# FTDIChip.net
KiCad netlist of a schematic drawn in Altium Designer
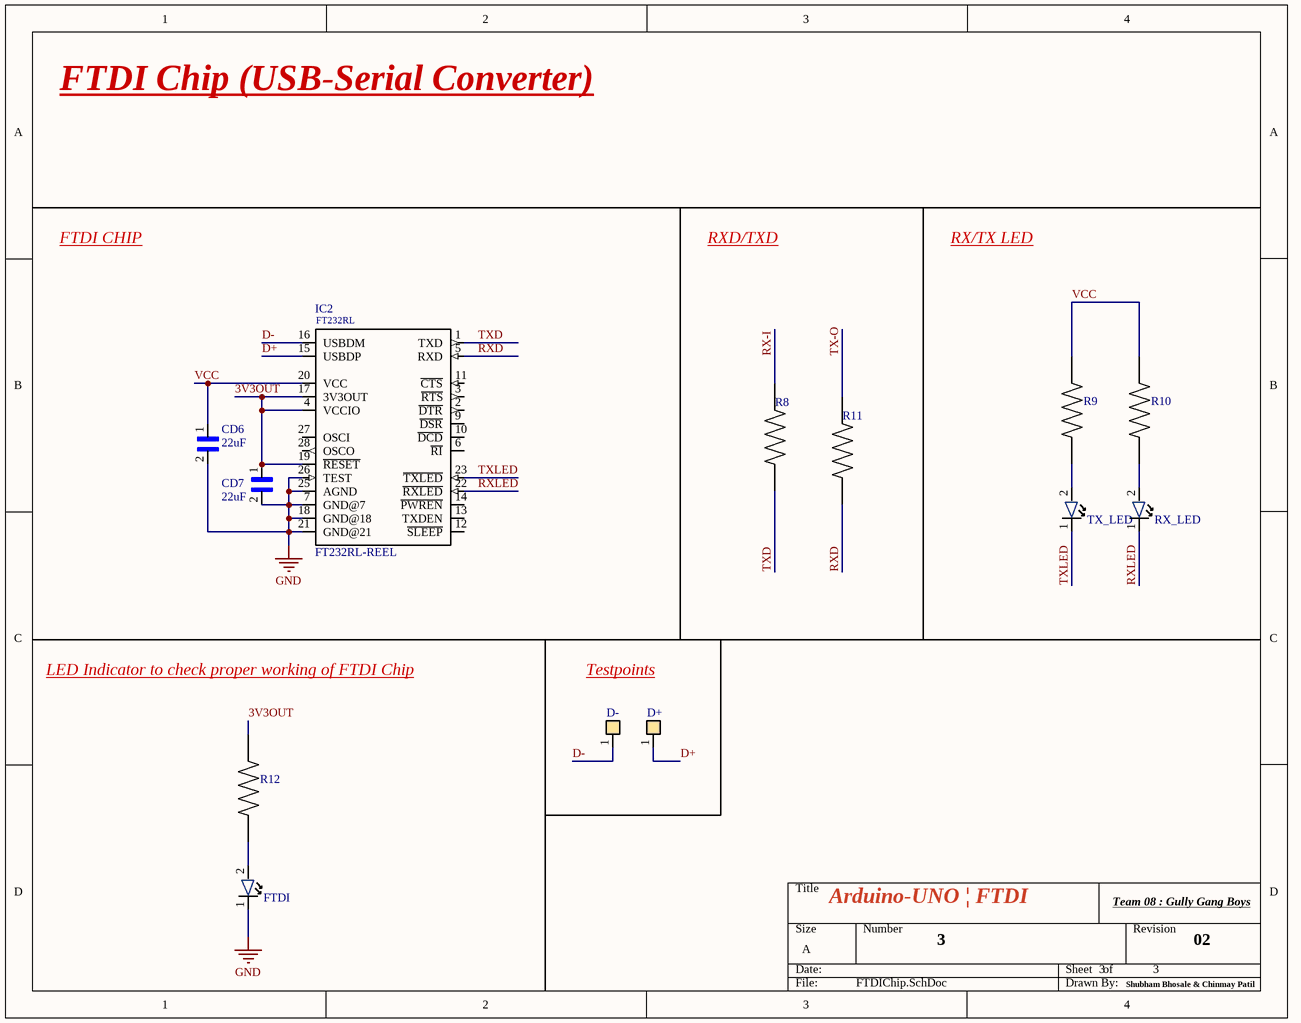
[diagram p0: FTDIChip.SchDoc]

(export (version "E")
  (design (tool "Eeschema 10.0.6"))
  (components
    (comp (ref "CD6")
      (value "22uF")
      (footprint "1206_Passive")
      (description "22µF ±20% 16V Ceramic Capacitor X5R 1206 (3216 Metric)")
      (fields (field (name "DIGIKEY PART") "1276-2728-1-ND"))
      (libsource (lib "brd2_rev2") (part "1206_22uF"))
    )
    (comp (ref "CD7")
      (value "22uF")
      (footprint "1206_Passive")
      (description "22µF ±20% 16V Ceramic Capacitor X5R 1206 (3216 Metric)")
      (fields (field (name "DIGIKEY PART") "1276-2728-1-ND"))
      (libsource (lib "brd2_rev2") (part "1206_22uF"))
    )
    (comp (ref "D+")
      (value "TESTPOINT")
      (footprint "TEST POINT")
      (libsource (lib "brd2_rev2") (part "TEST POINT"))
    )
    (comp (ref "D-")
      (value "TESTPOINT")
      (footprint "TEST POINT")
      (libsource (lib "brd2_rev2") (part "TEST POINT"))
    )
    (comp (ref "FTDI")
      (value "LTST-C150CKT")
      (footprint "LED")
      (description "Red 638nm LED Indication - Discrete 1.8V 1206 (3216 Metric)")
      (fields (field (name "DIGIKEY PART") "160-1167-1-ND"))
      (libsource (lib "brd2_rev2") (part "1206_RED_LED"))
    )
    (comp (ref "IC2")
      (value "FT232RL-REEL")
      (footprint "FTDI")
      (description "USB Bridge, USB to UART USB 2.0 UART Interface 28-SSOP")
      (fields (field (name "DIGIKEY PART") "768-1007-1-ND"))
      (libsource (lib "brd2_rev2") (part "FTDI"))
    )
    (comp (ref "R8")
      (value "RNCP1206FTD1K00")
      (footprint "1206_Passive")
      (description "1 kOhms ±1% 0.5W, 1/2W Chip Resistor 1206 (3216 Metric) Anti-Sulfur, Moisture Resistant Thin Film")
      (fields (field (name "DIGIKEY PART") "RNCP1206FTD1K00CT-ND"))
      (libsource (lib "brd2_rev2") (part "1206_1K"))
    )
    (comp (ref "R9")
      (value "RNCP1206FTD1K00")
      (footprint "1206_Passive")
      (description "1 kOhms ±1% 0.5W, 1/2W Chip Resistor 1206 (3216 Metric) Anti-Sulfur, Moisture Resistant Thin Film")
      (fields (field (name "DIGIKEY PART") "RNCP1206FTD1K00CT-ND"))
      (libsource (lib "brd2_rev2") (part "1206_1K"))
    )
    (comp (ref "R10")
      (value "RNCP1206FTD1K00")
      (footprint "1206_Passive")
      (description "1 kOhms ±1% 0.5W, 1/2W Chip Resistor 1206 (3216 Metric) Anti-Sulfur, Moisture Resistant Thin Film")
      (fields (field (name "DIGIKEY PART") "RNCP1206FTD1K00CT-ND"))
      (libsource (lib "brd2_rev2") (part "1206_1K"))
    )
    (comp (ref "R11")
      (value "RNCP1206FTD1K00")
      (footprint "1206_Passive")
      (description "1 kOhms ±1% 0.5W, 1/2W Chip Resistor 1206 (3216 Metric) Anti-Sulfur, Moisture Resistant Thin Film")
      (fields (field (name "DIGIKEY PART") "RNCP1206FTD1K00CT-ND"))
      (libsource (lib "brd2_rev2") (part "1206_1K"))
    )
    (comp (ref "R12")
      (value "RNCP1206FTD1K00")
      (footprint "1206_Passive")
      (description "1 kOhms ±1% 0.5W, 1/2W Chip Resistor 1206 (3216 Metric) Anti-Sulfur, Moisture Resistant Thin Film")
      (fields (field (name "DIGIKEY PART") "RNCP1206FTD1K00CT-ND"))
      (libsource (lib "brd2_rev2") (part "1206_1K"))
    )
    (comp (ref "RX_LED")
      (value "LTST-C150CKT")
      (footprint "LED")
      (description "Red 638nm LED Indication - Discrete 1.8V 1206 (3216 Metric)")
      (fields (field (name "DIGIKEY PART") "160-1167-1-ND"))
      (libsource (lib "brd2_rev2") (part "1206_RED_LED"))
    )
    (comp (ref "TX_LED")
      (value "LTST-C150CKT")
      (footprint "LED")
      (description "Red 638nm LED Indication - Discrete 1.8V 1206 (3216 Metric)")
      (fields (field (name "DIGIKEY PART") "160-1167-1-ND"))
      (libsource (lib "brd2_rev2") (part "1206_RED_LED"))
    )
  )
  (nets
    (net (code "1") (name "/3V3OUT") (class "Default")
      (node (ref "CD7") (pin "1") (pinfunction "1_1") (pintype "passive"))
      (node (ref "IC2") (pin "17") (pinfunction "3V3OUT_17") (pintype "power_in"))
      (node (ref "IC2") (pin "19") (pinfunction "~{RESET}_19") (pintype "passive"))
      (node (ref "IC2") (pin "4") (pinfunction "VCCIO_4") (pintype "power_in"))
      (node (ref "R12") (pin "1") (pinfunction "1_1") (pintype "passive"))
    )
    (net (code "2") (name "/D+") (class "Default")
      (node (ref "D+") (pin "1") (pinfunction "1_1") (pintype "passive"))
      (node (ref "IC2") (pin "15") (pinfunction "USBDP_15") (pintype "bidirectional"))
    )
    (net (code "3") (name "/D-") (class "Default")
      (node (ref "D-") (pin "1") (pinfunction "1_1") (pintype "passive"))
      (node (ref "IC2") (pin "16") (pinfunction "USBDM_16") (pintype "bidirectional"))
    )
    (net (code "4") (name "/RX-I") (class "Default")
      (node (ref "R8") (pin "2") (pinfunction "2_2") (pintype "passive"))
    )
    (net (code "5") (name "/RXD") (class "Default")
      (node (ref "IC2") (pin "5") (pinfunction "RXD_5") (pintype "input"))
      (node (ref "R11") (pin "1") (pinfunction "1_1") (pintype "passive"))
    )
    (net (code "6") (name "/RXLED") (class "Default")
      (node (ref "IC2") (pin "22") (pinfunction "~{RXLED}_22") (pintype "input"))
      (node (ref "RX_LED") (pin "1") (pinfunction "1_1") (pintype "passive"))
    )
    (net (code "7") (name "/TX-O") (class "Default")
      (node (ref "R11") (pin "2") (pinfunction "2_2") (pintype "passive"))
    )
    (net (code "8") (name "/TXD") (class "Default")
      (node (ref "IC2") (pin "1") (pinfunction "TXD_1") (pintype "output"))
      (node (ref "R8") (pin "1") (pinfunction "1_1") (pintype "passive"))
    )
    (net (code "9") (name "/TXLED") (class "Default")
      (node (ref "IC2") (pin "23") (pinfunction "~{TXLED}_23") (pintype "input"))
      (node (ref "TX_LED") (pin "1") (pinfunction "1_1") (pintype "passive"))
    )
    (net (code "10") (name "/VCC") (class "Default")
      (node (ref "CD6") (pin "1") (pinfunction "1_1") (pintype "passive"))
      (node (ref "IC2") (pin "20") (pinfunction "VCC_20") (pintype "power_in"))
      (node (ref "R10") (pin "1") (pinfunction "1_1") (pintype "passive"))
      (node (ref "R9") (pin "1") (pinfunction "1_1") (pintype "passive"))
    )
    (net (code "11") (name "GND") (class "Default")
      (node (ref "CD6") (pin "2") (pinfunction "2_2") (pintype "passive"))
      (node (ref "CD7") (pin "2") (pinfunction "2_2") (pintype "passive"))
      (node (ref "FTDI") (pin "1") (pinfunction "1_1") (pintype "passive"))
      (node (ref "IC2") (pin "18") (pinfunction "GND@18_18") (pintype "power_in"))
      (node (ref "IC2") (pin "21") (pinfunction "GND@21_21") (pintype "power_in"))
      (node (ref "IC2") (pin "25") (pinfunction "AGND_25") (pintype "power_in"))
      (node (ref "IC2") (pin "26") (pinfunction "TEST_26") (pintype "input"))
      (node (ref "IC2") (pin "7") (pinfunction "GND@7_7") (pintype "power_in"))
    )
    (net (code "12") (name "Net-(FTDI-Pad2)") (class "Default")
      (node (ref "FTDI") (pin "2") (pinfunction "2_2") (pintype "passive"))
      (node (ref "R12") (pin "2") (pinfunction "2_2") (pintype "passive"))
    )
    (net (code "13") (name "Net-(R9-Pad2)") (class "Default")
      (node (ref "R9") (pin "2") (pinfunction "2_2") (pintype "passive"))
      (node (ref "TX_LED") (pin "2") (pinfunction "2_2") (pintype "passive"))
    )
    (net (code "14") (name "Net-(R10-Pad2)") (class "Default")
      (node (ref "R10") (pin "2") (pinfunction "2_2") (pintype "passive"))
      (node (ref "RX_LED") (pin "2") (pinfunction "2_2") (pintype "passive"))
    )
    (net (code "15") (name "unconnected-(IC2-OSCI-Pad27)") (class "Default")
      (node (ref "IC2") (pin "27") (pinfunction "OSCI_27") (pintype "passive"))
    )
    (net (code "16") (name "unconnected-(IC2-OSCO-Pad28)") (class "Default")
      (node (ref "IC2") (pin "28") (pinfunction "OSCO_28") (pintype "output"))
    )
    (net (code "17") (name "unconnected-(IC2-TXDEN-Pad13)") (class "Default")
      (node (ref "IC2") (pin "13") (pinfunction "TXDEN_13") (pintype "passive"))
    )
    (net (code "18") (name "unconnected-(IC2-~{CTS}-Pad11)") (class "Default")
      (node (ref "IC2") (pin "11") (pinfunction "~{CTS}_11") (pintype "input"))
    )
    (net (code "19") (name "unconnected-(IC2-~{DCD}-Pad10)") (class "Default")
      (node (ref "IC2") (pin "10") (pinfunction "~{DCD}_10") (pintype "passive"))
    )
    (net (code "20") (name "unconnected-(IC2-~{DSR}-Pad9)") (class "Default")
      (node (ref "IC2") (pin "9") (pinfunction "~{DSR}_9") (pintype "passive"))
    )
    (net (code "21") (name "unconnected-(IC2-~{DTR}-Pad2)") (class "Default")
      (node (ref "IC2") (pin "2") (pinfunction "~{DTR}_2") (pintype "output"))
    )
    (net (code "22") (name "unconnected-(IC2-~{PWREN}-Pad14)") (class "Default")
      (node (ref "IC2") (pin "14") (pinfunction "~{PWREN}_14") (pintype "passive"))
    )
    (net (code "23") (name "unconnected-(IC2-~{RI}-Pad6)") (class "Default")
      (node (ref "IC2") (pin "6") (pinfunction "~{RI}_6") (pintype "passive"))
    )
    (net (code "24") (name "unconnected-(IC2-~{RTS}-Pad3)") (class "Default")
      (node (ref "IC2") (pin "3") (pinfunction "~{RTS}_3") (pintype "output"))
    )
    (net (code "25") (name "unconnected-(IC2-~{SLEEP}-Pad12)") (class "Default")
      (node (ref "IC2") (pin "12") (pinfunction "~{SLEEP}_12") (pintype "passive"))
    )
  )
)
